# Nusbio_smd.net
KiCad netlist of a schematic drawn in EAGLE
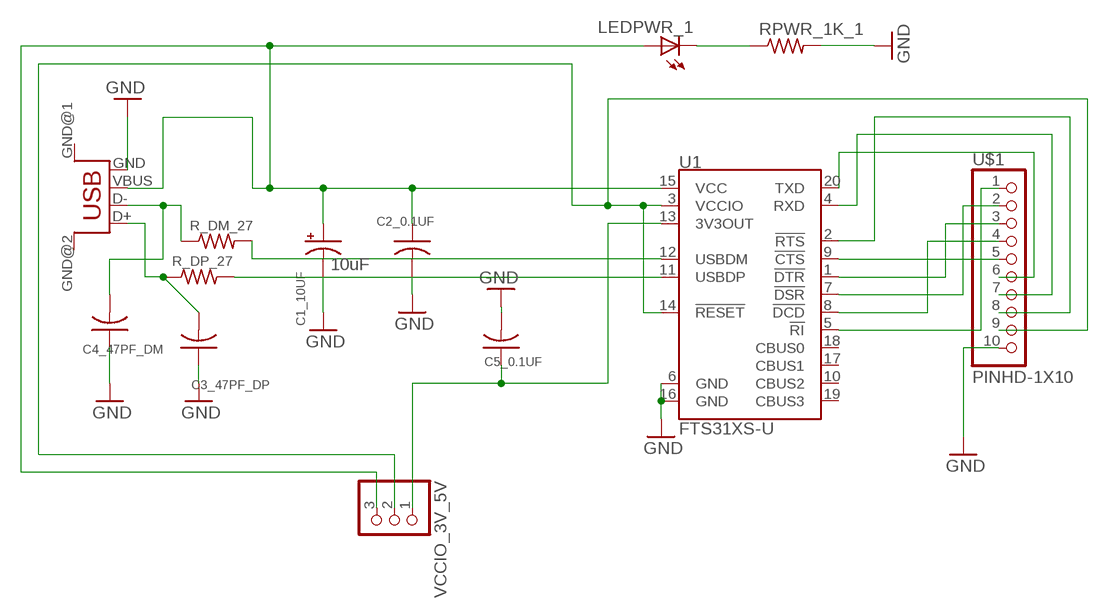
[diagram p0: schematic, sheet 1]

(export (version "E")
  (design (tool "Eeschema 10.0.6"))
  (components
    (comp (ref "C1_10UF")
      (value "10uF")
      (footprint "eagle-import:EIA3216")
      (libsource (lib "eagle-import") (part "10UF-16V-10%(TANT)"))
    )
    (comp (ref "C2_0.1UF")
      (value "C-USC1206")
      (footprint "eagle-import:C1206")
      (libsource (lib "eagle-import") (part "C-USC1206"))
    )
    (comp (ref "C3_47PF_DP")
      (value "C-USC1206")
      (footprint "eagle-import:C1206")
      (libsource (lib "eagle-import") (part "C-USC1206"))
    )
    (comp (ref "C4_47PF_DM")
      (value "C-USC1206")
      (footprint "eagle-import:C1206")
      (libsource (lib "eagle-import") (part "C-USC1206"))
    )
    (comp (ref "C5_0.1UF")
      (value "C-USC1206")
      (footprint "eagle-import:C1206")
      (libsource (lib "eagle-import") (part "C-USC1206"))
    )
    (comp (ref "LEDPWR_1")
      (value "LEDCHIPLED_0805")
      (footprint "eagle-import:CHIPLED_0805")
      (libsource (lib "eagle-import") (part "LEDCHIPLED_0805"))
    )
    (comp (ref "RPWR_1K_1")
      (value "R-US_R0805")
      (footprint "eagle-import:R0805")
      (libsource (lib "eagle-import") (part "R-US_R0805"))
    )
    (comp (ref "R_DM_27")
      (value "R-US_R0805")
      (footprint "eagle-import:R0805")
      (libsource (lib "eagle-import") (part "R-US_R0805"))
    )
    (comp (ref "R_DP_27")
      (value "R-US_R0805")
      (footprint "eagle-import:R0805")
      (libsource (lib "eagle-import") (part "R-US_R0805"))
    )
    (comp (ref "U$1")
      (value "PINHD-1X10")
      (footprint "eagle-import:1X10-BIG")
      (libsource (lib "eagle-import") (part "PINHD-1X10"))
    )
    (comp (ref "U1")
      (value "FTS31XS-U")
      (footprint "eagle-import:SSOP20_L")
      (libsource (lib "eagle-import") (part "FT231XS"))
    )
    (comp (ref "USB_FEMALE")
      (value "USB")
      (footprint "eagle-import:USB-FEMALE-A-PTH")
      (libsource (lib "eagle-import") (part "USB"))
    )
    (comp (ref "VCCIO_3V_5V")
      (value "PINHD-1X3")
      (footprint "eagle-import:1X03")
      (libsource (lib "eagle-import") (part "PINHD-1X3"))
    )
  )
  (nets
    (net (code "1") (name "GND") (class "Default")
      (node (ref "C1_10UF") (pin "C") (pinfunction "-_C") (pintype "passive"))
      (node (ref "C2_0.1UF") (pin "2") (pinfunction "2_2") (pintype "passive"))
      (node (ref "C3_47PF_DP") (pin "1") (pinfunction "1_1") (pintype "passive"))
      (node (ref "C4_47PF_DM") (pin "1") (pinfunction "1_1") (pintype "passive"))
      (node (ref "C5_0.1UF") (pin "2") (pinfunction "2_2") (pintype "passive"))
      (node (ref "RPWR_1K_1") (pin "2") (pinfunction "2_2") (pintype "passive"))
      (node (ref "U$1") (pin "10") (pinfunction "10_10") (pintype "passive"))
      (node (ref "U1") (pin "16") (pinfunction "GND_16") (pintype "bidirectional"))
      (node (ref "U1") (pin "6") (pinfunction "GND_6") (pintype "bidirectional"))
      (node (ref "USB_FEMALE") (pin "GND") (pinfunction "GND_GND") (pintype "bidirectional"))
    )
    (net (code "2") (name "Net-(C1_10UF-+)") (class "Default")
      (node (ref "C1_10UF") (pin "A") (pinfunction "+_A") (pintype "passive"))
      (node (ref "C2_0.1UF") (pin "1") (pinfunction "1_1") (pintype "passive"))
      (node (ref "LEDPWR_1") (pin "A") (pinfunction "A_A") (pintype "passive"))
      (node (ref "U1") (pin "15") (pinfunction "VCC_15") (pintype "bidirectional"))
      (node (ref "USB_FEMALE") (pin "VBUS") (pinfunction "VBUS_VBUS") (pintype "bidirectional"))
      (node (ref "VCCIO_3V_5V") (pin "3") (pinfunction "3_3") (pintype "passive"))
    )
    (net (code "3") (name "Net-(C3_47PF_DP-Pad2)") (class "Default")
      (node (ref "C3_47PF_DP") (pin "2") (pinfunction "2_2") (pintype "passive"))
      (node (ref "R_DP_27") (pin "1") (pinfunction "1_1") (pintype "passive"))
      (node (ref "USB_FEMALE") (pin "D+") (pinfunction "D+_D+") (pintype "bidirectional"))
    )
    (net (code "4") (name "Net-(C4_47PF_DM-Pad2)") (class "Default")
      (node (ref "C4_47PF_DM") (pin "2") (pinfunction "2_2") (pintype "passive"))
      (node (ref "R_DM_27") (pin "1") (pinfunction "1_1") (pintype "passive"))
      (node (ref "USB_FEMALE") (pin "D-") (pinfunction "D-_D-") (pintype "bidirectional"))
    )
    (net (code "5") (name "Net-(LEDPWR_1-PadC)") (class "Default")
      (node (ref "LEDPWR_1") (pin "C") (pinfunction "C_C") (pintype "passive"))
      (node (ref "RPWR_1K_1") (pin "1") (pinfunction "1_1") (pintype "passive"))
    )
    (net (code "6") (name "Net-(U1-3V3OUT)") (class "Default")
      (node (ref "C5_0.1UF") (pin "1") (pinfunction "1_1") (pintype "passive"))
      (node (ref "U1") (pin "13") (pinfunction "3V3OUT_13") (pintype "bidirectional"))
      (node (ref "VCCIO_3V_5V") (pin "1") (pinfunction "1_1") (pintype "passive"))
    )
    (net (code "7") (name "Net-(U1-RXD)") (class "Default")
      (node (ref "U$1") (pin "7") (pinfunction "7_7") (pintype "passive"))
      (node (ref "U1") (pin "4") (pinfunction "RXD_4") (pintype "bidirectional"))
    )
    (net (code "8") (name "Net-(U1-TXD)") (class "Default")
      (node (ref "U$1") (pin "6") (pinfunction "6_6") (pintype "passive"))
      (node (ref "U1") (pin "20") (pinfunction "TXD_20") (pintype "bidirectional"))
    )
    (net (code "9") (name "Net-(U1-USBDM)") (class "Default")
      (node (ref "R_DM_27") (pin "2") (pinfunction "2_2") (pintype "passive"))
      (node (ref "U1") (pin "12") (pinfunction "USBDM_12") (pintype "bidirectional"))
    )
    (net (code "10") (name "Net-(U1-USBDP)") (class "Default")
      (node (ref "R_DP_27") (pin "2") (pinfunction "2_2") (pintype "passive"))
      (node (ref "U1") (pin "11") (pinfunction "USBDP_11") (pintype "bidirectional"))
    )
    (net (code "11") (name "Net-(U1-VCCIO)") (class "Default")
      (node (ref "U$1") (pin "9") (pinfunction "9_9") (pintype "passive"))
      (node (ref "U1") (pin "14") (pinfunction "~{RESET}_14") (pintype "bidirectional"))
      (node (ref "U1") (pin "3") (pinfunction "VCCIO_3") (pintype "bidirectional"))
      (node (ref "VCCIO_3V_5V") (pin "2") (pinfunction "2_2") (pintype "passive"))
    )
    (net (code "12") (name "Net-(U1-~{CTS})") (class "Default")
      (node (ref "U$1") (pin "5") (pinfunction "5_5") (pintype "passive"))
      (node (ref "U1") (pin "9") (pinfunction "~{CTS}_9") (pintype "bidirectional"))
    )
    (net (code "13") (name "Net-(U1-~{DCD})") (class "Default")
      (node (ref "U$1") (pin "4") (pinfunction "4_4") (pintype "passive"))
      (node (ref "U1") (pin "8") (pinfunction "~{DCD}_8") (pintype "bidirectional"))
    )
    (net (code "14") (name "Net-(U1-~{DSR})") (class "Default")
      (node (ref "U$1") (pin "2") (pinfunction "2_2") (pintype "passive"))
      (node (ref "U1") (pin "7") (pinfunction "~{DSR}_7") (pintype "bidirectional"))
    )
    (net (code "15") (name "Net-(U1-~{DTR})") (class "Default")
      (node (ref "U$1") (pin "3") (pinfunction "3_3") (pintype "passive"))
      (node (ref "U1") (pin "1") (pinfunction "~{DTR}_1") (pintype "bidirectional"))
    )
    (net (code "16") (name "Net-(U1-~{RI})") (class "Default")
      (node (ref "U$1") (pin "1") (pinfunction "1_1") (pintype "passive"))
      (node (ref "U1") (pin "5") (pinfunction "~{RI}_5") (pintype "bidirectional"))
    )
    (net (code "17") (name "Net-(U1-~{RTS})") (class "Default")
      (node (ref "U$1") (pin "8") (pinfunction "8_8") (pintype "passive"))
      (node (ref "U1") (pin "2") (pinfunction "~{RTS}_2") (pintype "bidirectional"))
    )
    (net (code "18") (name "unconnected-(U1-CBUS0-Pad18)") (class "Default")
      (node (ref "U1") (pin "18") (pinfunction "CBUS0_18") (pintype "bidirectional"))
    )
    (net (code "19") (name "unconnected-(U1-CBUS1-Pad17)") (class "Default")
      (node (ref "U1") (pin "17") (pinfunction "CBUS1_17") (pintype "bidirectional"))
    )
    (net (code "20") (name "unconnected-(U1-CBUS2-Pad10)") (class "Default")
      (node (ref "U1") (pin "10") (pinfunction "CBUS2_10") (pintype "bidirectional"))
    )
    (net (code "21") (name "unconnected-(U1-CBUS3-Pad19)") (class "Default")
      (node (ref "U1") (pin "19") (pinfunction "CBUS3_19") (pintype "bidirectional"))
    )
    (net (code "22") (name "unconnected-(USB_FEMALE-GND-PadGND@1)") (class "Default")
      (node (ref "USB_FEMALE") (pin "GND@1") (pinfunction "GND_GND@1") (pintype "bidirectional"))
    )
    (net (code "23") (name "unconnected-(USB_FEMALE-GND-PadGND@2)") (class "Default")
      (node (ref "USB_FEMALE") (pin "GND@2") (pinfunction "GND_GND@2") (pintype "bidirectional"))
    )
  )
)
